# EEZ_DIB_BP3C_r3B1.net
KiCad netlist of a schematic drawn in EAGLE
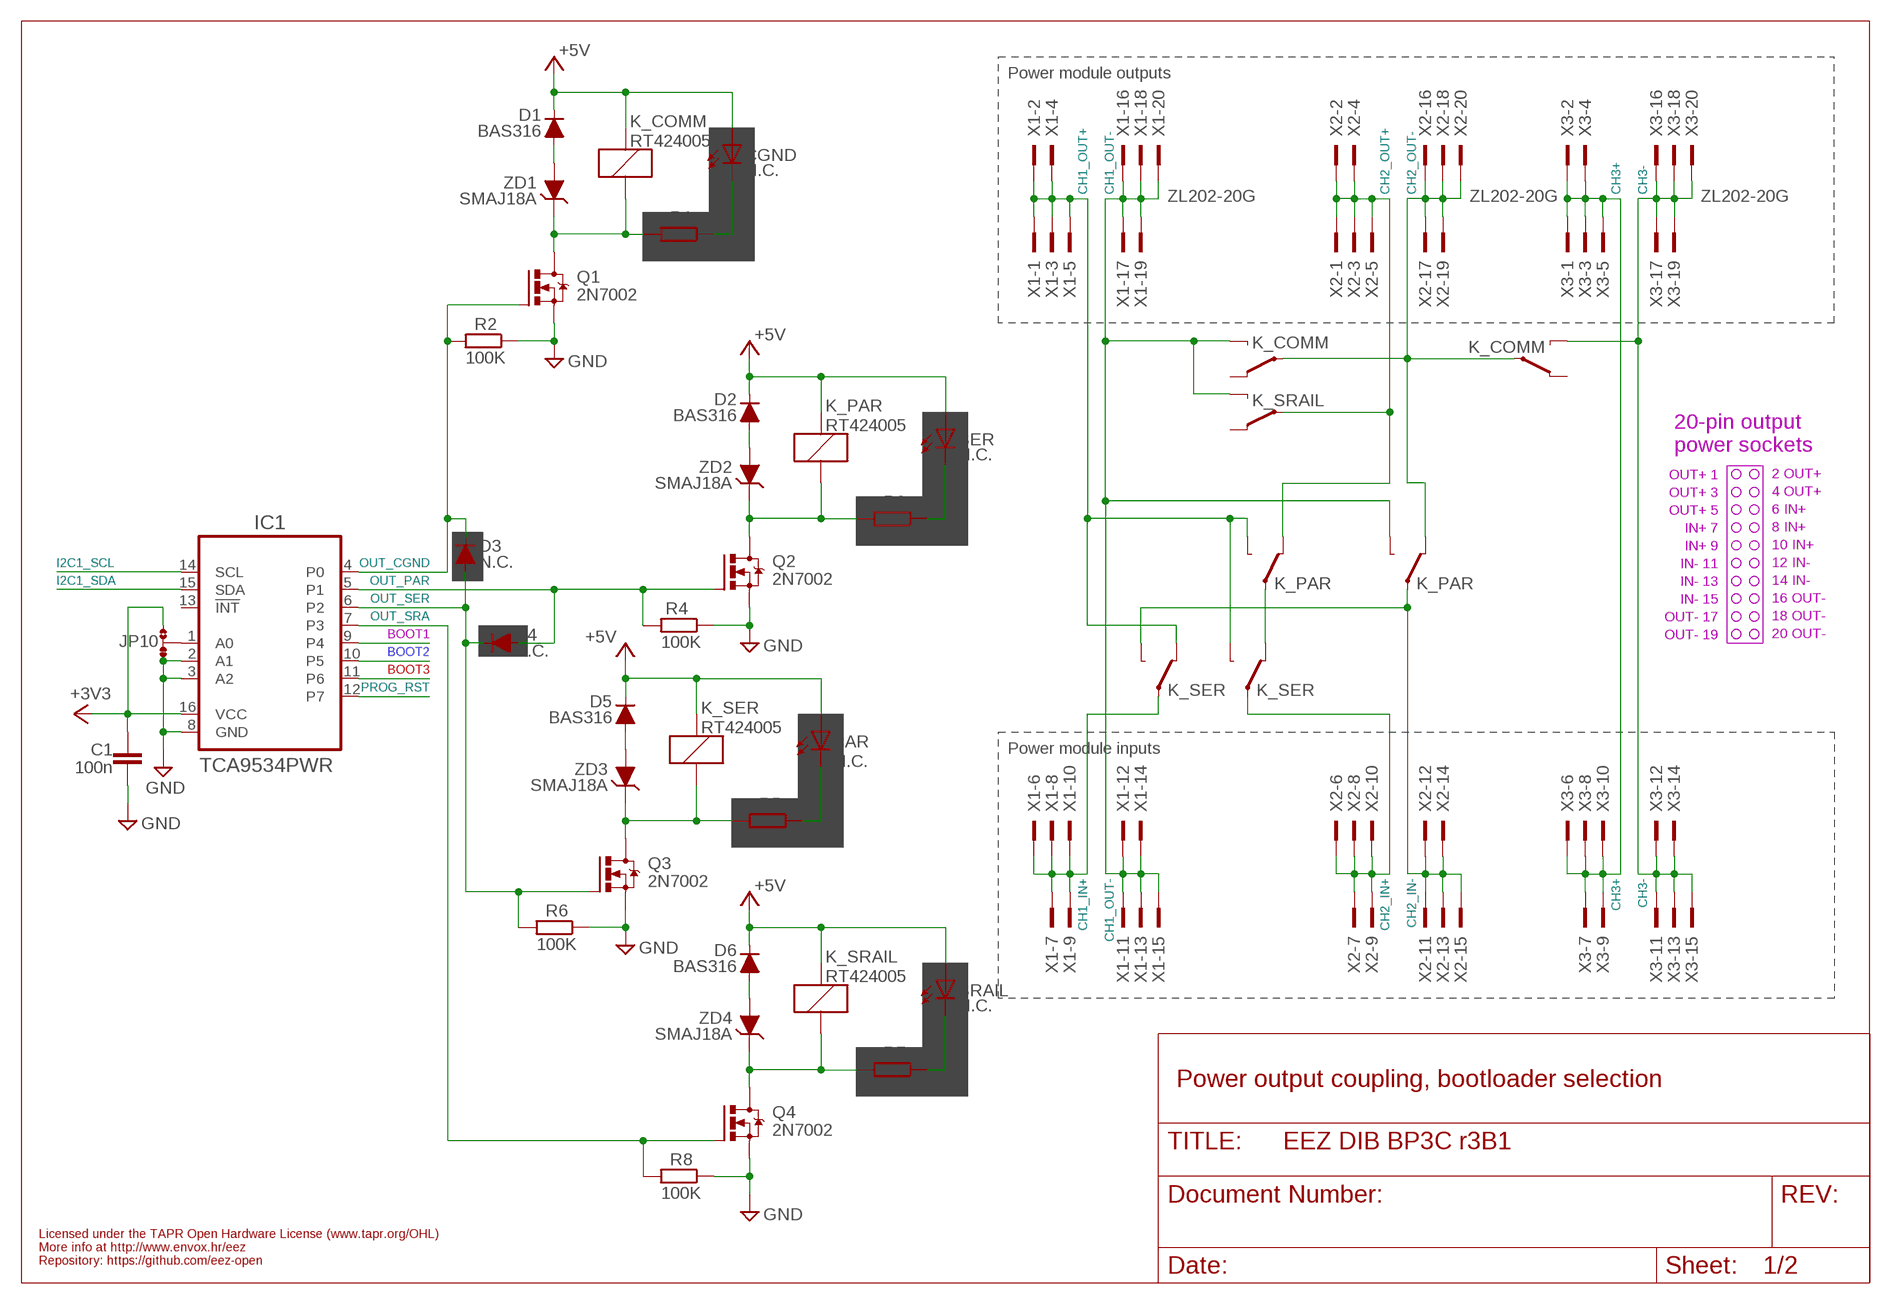
[diagram p0: schematic, sheet 1]
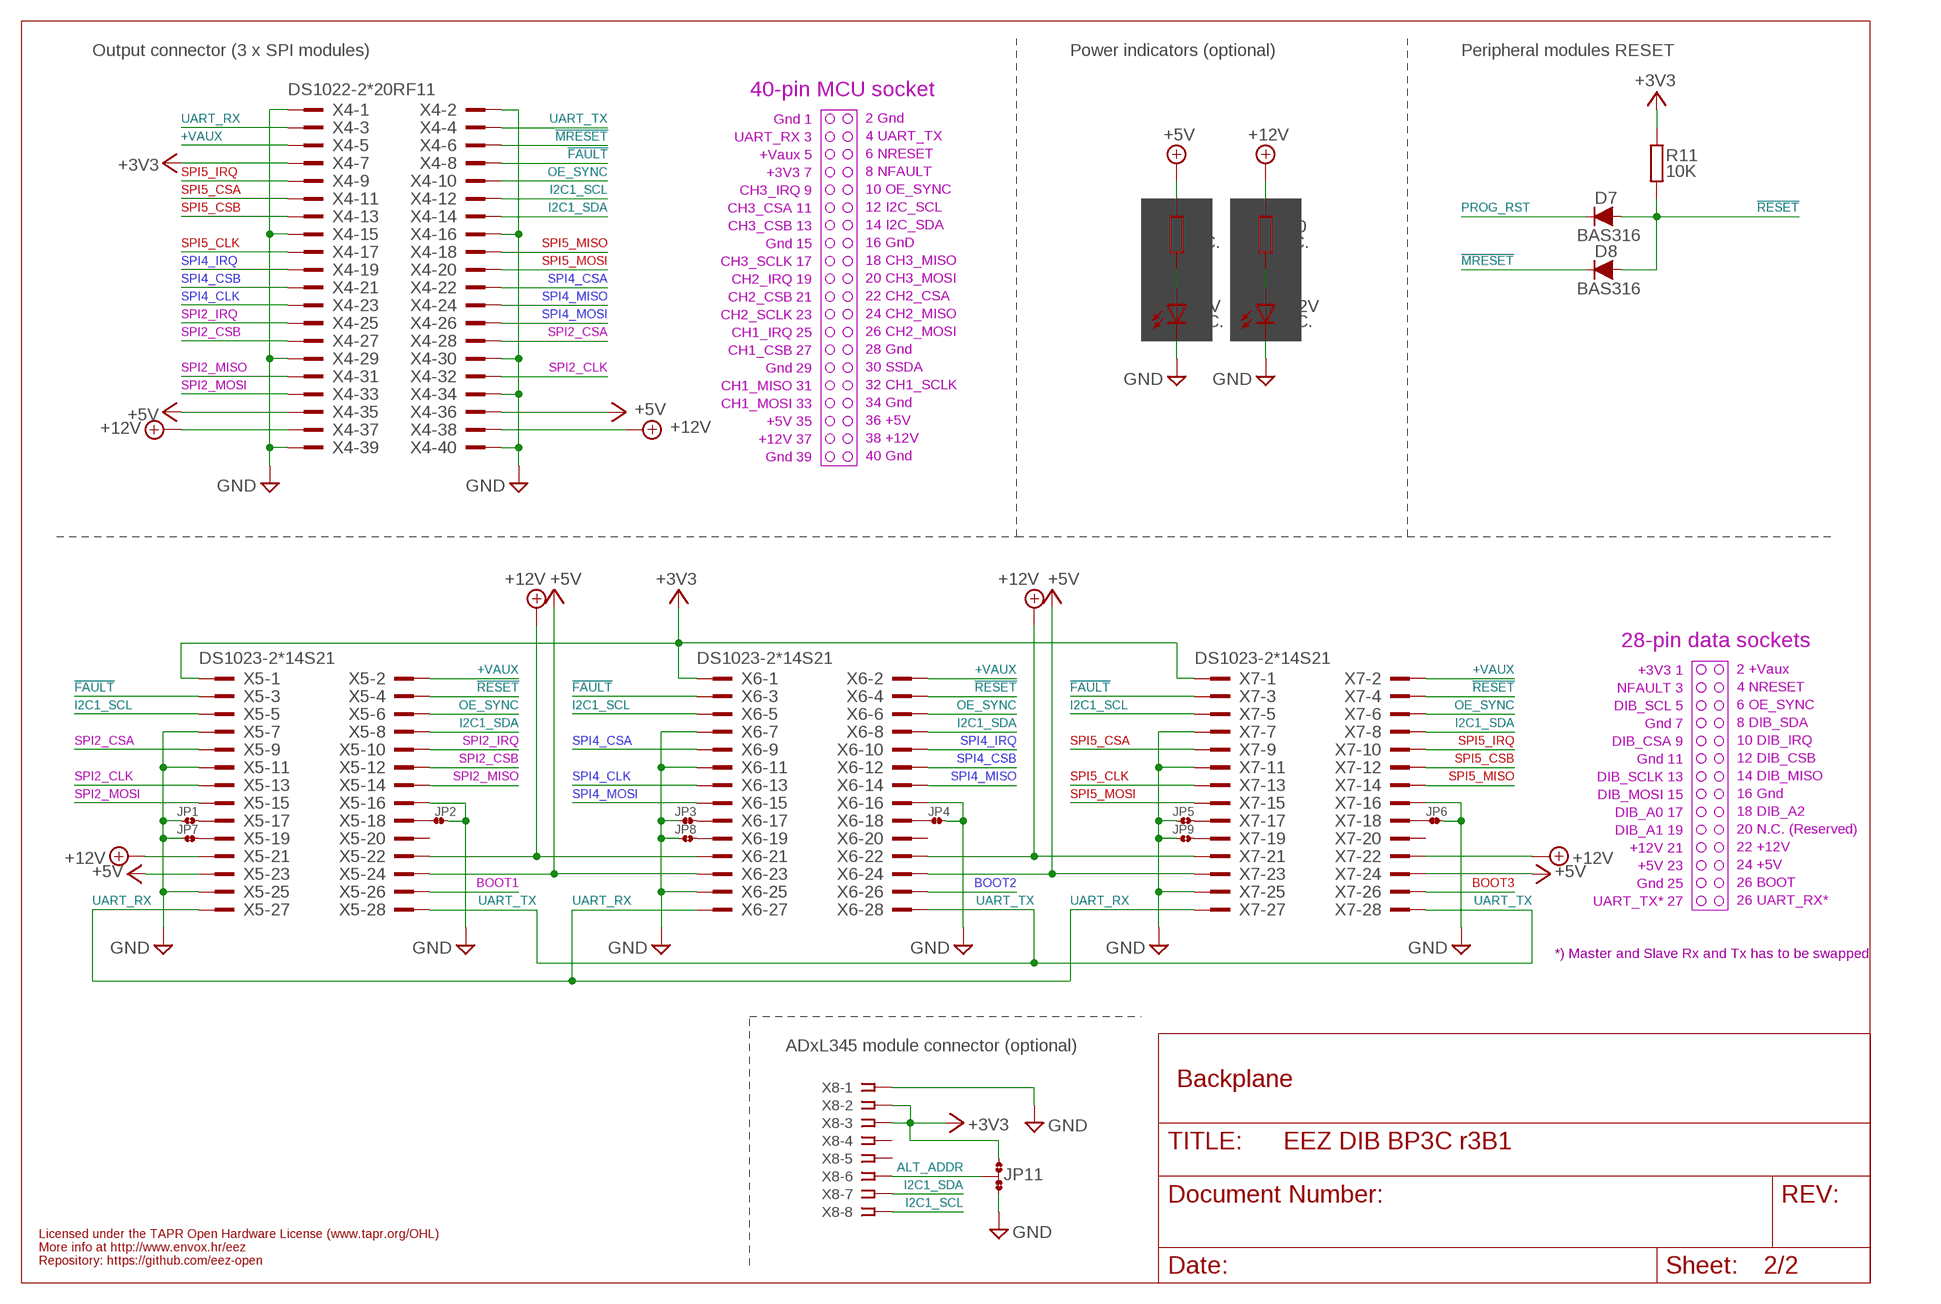
[diagram p1: schematic, sheet 2]

(export (version "E")
  (design (tool "Eeschema 10.0.6"))
  (components
    (comp (ref "+5V")
      (value "N.C.")
      (footprint "eagle-import:LED_0805")
      (libsource (lib "eagle-import") (part "LED0805"))
    )
    (comp (ref "+12V")
      (value "N.C.")
      (footprint "eagle-import:LED_0805")
      (libsource (lib "eagle-import") (part "LED0805"))
    )
    (comp (ref "D7")
      (value "BAS316")
      (footprint "eagle-import:SOD323-R")
      (libsource (lib "eagle-import") (part "DIODESOD323R"))
    )
    (comp (ref "D8")
      (value "BAS316")
      (footprint "eagle-import:SOD323-R")
      (libsource (lib "eagle-import") (part "DIODESOD323R"))
    )
    (comp (ref "JP1")
      (value "JP2-CUT")
      (footprint "eagle-import:JP2-CUT")
      (libsource (lib "eagle-import") (part "JP2-CUT"))
    )
    (comp (ref "JP2")
      (value "JP2-NOCUT")
      (footprint "eagle-import:JP2-NOCUT")
      (libsource (lib "eagle-import") (part "JP2-NOCUT"))
    )
    (comp (ref "JP3")
      (value "JP2-NOCUT")
      (footprint "eagle-import:JP2-NOCUT")
      (libsource (lib "eagle-import") (part "JP2-NOCUT"))
    )
    (comp (ref "JP4")
      (value "JP2-NOCUT")
      (footprint "eagle-import:JP2-NOCUT")
      (libsource (lib "eagle-import") (part "JP2-NOCUT"))
    )
    (comp (ref "JP5")
      (value "JP2-CUT")
      (footprint "eagle-import:JP2-CUT")
      (libsource (lib "eagle-import") (part "JP2-CUT"))
    )
    (comp (ref "JP6")
      (value "JP2-NOCUT")
      (footprint "eagle-import:JP2-NOCUT")
      (libsource (lib "eagle-import") (part "JP2-NOCUT"))
    )
    (comp (ref "JP7")
      (value "JP2-NOCUT")
      (footprint "eagle-import:JP2-NOCUT")
      (libsource (lib "eagle-import") (part "JP2-NOCUT"))
    )
    (comp (ref "JP8")
      (value "JP2-CUT")
      (footprint "eagle-import:JP2-CUT")
      (libsource (lib "eagle-import") (part "JP2-CUT"))
    )
    (comp (ref "JP9")
      (value "JP2-CUT")
      (footprint "eagle-import:JP2-CUT")
      (libsource (lib "eagle-import") (part "JP2-CUT"))
    )
    (comp (ref "JP11")
      (value "JP3-CUT")
      (footprint "eagle-import:JP3-CUT")
      (libsource (lib "eagle-import") (part "JP3-CUT"))
    )
    (comp (ref "R9")
      (value "N.C.")
      (footprint "eagle-import:R0805")
      (libsource (lib "eagle-import") (part "R-EU_R0805"))
    )
    (comp (ref "R10")
      (value "N.C.")
      (footprint "eagle-import:R0805")
      (libsource (lib "eagle-import") (part "R-EU_R0805"))
    )
    (comp (ref "R11")
      (value "10K")
      (footprint "eagle-import:R0805")
      (libsource (lib "eagle-import") (part "R-EU_R0805"))
    )
    (comp (ref "X4")
      (value "DS1022-2*20RF11")
      (footprint "eagle-import:ZL212-40KG")
      (libsource (lib "eagle-import") (part "ZL212-40KG"))
    )
    (comp (ref "X5")
      (value "DS1023-2*14S21")
      (footprint "eagle-import:TSW-114-07-F-D")
      (libsource (lib "eagle-import") (part "TSW-114-07-F-D"))
    )
    (comp (ref "X6")
      (value "DS1023-2*14S21")
      (footprint "eagle-import:TSW-114-07-F-D")
      (libsource (lib "eagle-import") (part "TSW-114-07-F-D"))
    )
    (comp (ref "X7")
      (value "DS1023-2*14S21")
      (footprint "eagle-import:TSW-114-07-F-D")
      (libsource (lib "eagle-import") (part "TSW-114-07-F-D"))
    )
    (comp (ref "X8")
      (value "N.C.")
      (footprint "eagle-import:SSW-108-02-S-S")
      (fields (field (name "MPN") "SSW-108-02-S-S"))
      (libsource (lib "eagle-import") (part "SSW-108-02-S-S"))
    )
    (comp (ref "C1")
      (value "100n")
      (footprint "eagle-import:C0603")
      (libsource (lib "eagle-import") (part "C-EUC0603"))
    )
    (comp (ref "CGND")
      (value "N.C.")
      (footprint "eagle-import:LED_0805")
      (libsource (lib "eagle-import") (part "LED0805"))
    )
    (comp (ref "D1")
      (value "BAS316")
      (footprint "eagle-import:SOD323-R")
      (libsource (lib "eagle-import") (part "DIODESOD323R"))
    )
    (comp (ref "D2")
      (value "BAS316")
      (footprint "eagle-import:SOD323-R")
      (libsource (lib "eagle-import") (part "DIODESOD323R"))
    )
    (comp (ref "D3")
      (value "N.C.")
      (footprint "eagle-import:SOD323-R")
      (libsource (lib "eagle-import") (part "DIODESOD323R"))
    )
    (comp (ref "D4")
      (value "N.C.")
      (footprint "eagle-import:SOD323-R")
      (libsource (lib "eagle-import") (part "DIODESOD323R"))
    )
    (comp (ref "D5")
      (value "BAS316")
      (footprint "eagle-import:SOD323-R")
      (libsource (lib "eagle-import") (part "DIODESOD323R"))
    )
    (comp (ref "D6")
      (value "BAS316")
      (footprint "eagle-import:SOD323-R")
      (libsource (lib "eagle-import") (part "DIODESOD323R"))
    )
    (comp (ref "IC1")
      (value "TCA9534PWR")
      (footprint "eagle-import:PW(R-PDSO-G16)")
      (libsource (lib "eagle-import") (part "TCA9534PWR"))
    )
    (comp (ref "JP10")
      (value "JP3-CUT")
      (footprint "eagle-import:JP3-CUT")
      (libsource (lib "eagle-import") (part "JP3-CUT"))
    )
    (comp (ref "K_COMM")
      (value "RT424005")
      (footprint "eagle-import:RT-C_016A5_ROUND")
      (libsource (lib "eagle-import") (part "RELAY_RT314012-2"))
    )
    (comp (ref "K_PAR")
      (value "RT424005")
      (footprint "eagle-import:RT-C_016A5_ROUND")
      (libsource (lib "eagle-import") (part "RELAY_RT314012-2"))
    )
    (comp (ref "K_SER")
      (value "RT424005")
      (footprint "eagle-import:RT-C_016A5_ROUND")
      (libsource (lib "eagle-import") (part "RELAY_RT314012-2"))
    )
    (comp (ref "K_SRAIL")
      (value "RT424005")
      (footprint "eagle-import:RT-C_016A5_ROUND")
      (libsource (lib "eagle-import") (part "RELAY_RT314012-2"))
    )
    (comp (ref "PAR")
      (value "N.C.")
      (footprint "eagle-import:LED_0805")
      (libsource (lib "eagle-import") (part "LED0805"))
    )
    (comp (ref "Q1")
      (value "2N7002")
      (footprint "eagle-import:SOT103P240X110-3N")
      (fields
        (field (name "MPN") "2N7002-7-F")
        (field (name "MPN_1") "2N7002-7-F")
        (field (name "OC_FARNELL") "1713823")
        (field (name "OC_NEWARK") "25R5679")
        (field (name "PACKAGE") "SOT-23-3")
        (field (name "SUPPLIER") "DIODES INC.")
      )
      (libsource (lib "eagle-import") (part "2N7002"))
    )
    (comp (ref "Q2")
      (value "2N7002")
      (footprint "eagle-import:SOT103P240X110-3N")
      (fields
        (field (name "MPN") "2N7002-7-F")
        (field (name "MPN_1") "2N7002-7-F")
        (field (name "OC_FARNELL") "1713823")
        (field (name "OC_NEWARK") "25R5679")
        (field (name "PACKAGE") "SOT-23-3")
        (field (name "SUPPLIER") "DIODES INC.")
      )
      (libsource (lib "eagle-import") (part "2N7002"))
    )
    (comp (ref "Q3")
      (value "2N7002")
      (footprint "eagle-import:SOT103P240X110-3N")
      (fields
        (field (name "MPN") "2N7002-7-F")
        (field (name "MPN_1") "2N7002-7-F")
        (field (name "OC_FARNELL") "1713823")
        (field (name "OC_NEWARK") "25R5679")
        (field (name "PACKAGE") "SOT-23-3")
        (field (name "SUPPLIER") "DIODES INC.")
      )
      (libsource (lib "eagle-import") (part "2N7002"))
    )
    (comp (ref "Q4")
      (value "2N7002")
      (footprint "eagle-import:SOT103P240X110-3N")
      (fields
        (field (name "MPN") "2N7002-7-F")
        (field (name "MPN_1") "2N7002-7-F")
        (field (name "OC_FARNELL") "1713823")
        (field (name "OC_NEWARK") "25R5679")
        (field (name "PACKAGE") "SOT-23-3")
        (field (name "SUPPLIER") "DIODES INC.")
      )
      (libsource (lib "eagle-import") (part "2N7002"))
    )
    (comp (ref "R1")
      (value "N.C.")
      (footprint "eagle-import:R0805")
      (libsource (lib "eagle-import") (part "R-EU_R0805"))
    )
    (comp (ref "R2")
      (value "100K")
      (footprint "eagle-import:R0805")
      (libsource (lib "eagle-import") (part "R-EU_R0805"))
    )
    (comp (ref "R3")
      (value "N.C.")
      (footprint "eagle-import:R0805")
      (libsource (lib "eagle-import") (part "R-EU_R0805"))
    )
    (comp (ref "R4")
      (value "100K")
      (footprint "eagle-import:R0805")
      (libsource (lib "eagle-import") (part "R-EU_R0805"))
    )
    (comp (ref "R5")
      (value "N.C.")
      (footprint "eagle-import:R0805")
      (libsource (lib "eagle-import") (part "R-EU_R0805"))
    )
    (comp (ref "R6")
      (value "100K")
      (footprint "eagle-import:R0805")
      (libsource (lib "eagle-import") (part "R-EU_R0805"))
    )
    (comp (ref "R7")
      (value "N.C.")
      (footprint "eagle-import:R0805")
      (libsource (lib "eagle-import") (part "R-EU_R0805"))
    )
    (comp (ref "R8")
      (value "100K")
      (footprint "eagle-import:R0805")
      (libsource (lib "eagle-import") (part "R-EU_R0805"))
    )
    (comp (ref "SER")
      (value "N.C.")
      (footprint "eagle-import:LED_0805")
      (libsource (lib "eagle-import") (part "LED0805"))
    )
    (comp (ref "SRAIL")
      (value "N.C.")
      (footprint "eagle-import:LED_0805")
      (libsource (lib "eagle-import") (part "LED0805"))
    )
    (comp (ref "X1")
      (value "ZL202-20G")
      (footprint "eagle-import:DS1021-2_10SF11")
      (libsource (lib "eagle-import") (part "DS1021-210SF11"))
    )
    (comp (ref "X2")
      (value "ZL202-20G")
      (footprint "eagle-import:DS1021-2_10SF11")
      (libsource (lib "eagle-import") (part "DS1021-210SF11"))
    )
    (comp (ref "X3")
      (value "ZL202-20G")
      (footprint "eagle-import:DS1021-2_10SF11")
      (libsource (lib "eagle-import") (part "DS1021-210SF11"))
    )
    (comp (ref "ZD1")
      (value "SMAJ18A")
      (footprint "eagle-import:DO214AC")
      (libsource (lib "eagle-import") (part "PSMAXX"))
    )
    (comp (ref "ZD2")
      (value "SMAJ18A")
      (footprint "eagle-import:DO214AC")
      (libsource (lib "eagle-import") (part "PSMAXX"))
    )
    (comp (ref "ZD3")
      (value "SMAJ18A")
      (footprint "eagle-import:DO214AC")
      (libsource (lib "eagle-import") (part "PSMAXX"))
    )
    (comp (ref "ZD4")
      (value "SMAJ18A")
      (footprint "eagle-import:DO214AC")
      (libsource (lib "eagle-import") (part "PSMAXX"))
    )
  )
  (nets
    (net (code "1") (name "+3V3") (class "Default")
      (node (ref "C1") (pin "1") (pinfunction "1_1") (pintype "passive"))
      (node (ref "IC1") (pin "16") (pinfunction "VCC_16") (pintype "passive"))
      (node (ref "JP10") (pin "NO") (pinfunction "NO_NO") (pintype "passive"))
      (node (ref "JP11") (pin "NO") (pinfunction "NO_NO") (pintype "passive"))
      (node (ref "R11") (pin "1") (pinfunction "1_1") (pintype "passive"))
      (node (ref "X4") (pin "7") (pinfunction "1_7") (pintype "passive"))
      (node (ref "X5") (pin "1") (pinfunction "1_1") (pintype "passive"))
      (node (ref "X6") (pin "1") (pinfunction "1_1") (pintype "passive"))
      (node (ref "X7") (pin "1") (pinfunction "1_1") (pintype "passive"))
      (node (ref "X8") (pin "2") (pinfunction "1_2") (pintype "passive"))
      (node (ref "X8") (pin "3") (pinfunction "1_3") (pintype "passive"))
    )
    (net (code "2") (name "+5V") (class "Default")
      (node (ref "CGND") (pin "A") (pinfunction "A_A") (pintype "passive"))
      (node (ref "D1") (pin "C") (pinfunction "C_C") (pintype "passive"))
      (node (ref "D2") (pin "C") (pinfunction "C_C") (pintype "passive"))
      (node (ref "D5") (pin "C") (pinfunction "C_C") (pintype "passive"))
      (node (ref "D6") (pin "C") (pinfunction "C_C") (pintype "passive"))
      (node (ref "K_COMM") (pin "A2") (pinfunction "C1_A2") (pintype "passive"))
      (node (ref "K_PAR") (pin "A2") (pinfunction "C1_A2") (pintype "passive"))
      (node (ref "K_SER") (pin "A2") (pinfunction "C1_A2") (pintype "passive"))
      (node (ref "K_SRAIL") (pin "A2") (pinfunction "C1_A2") (pintype "passive"))
      (node (ref "PAR") (pin "A") (pinfunction "A_A") (pintype "passive"))
      (node (ref "R9") (pin "1") (pinfunction "1_1") (pintype "passive"))
      (node (ref "SER") (pin "A") (pinfunction "A_A") (pintype "passive"))
      (node (ref "SRAIL") (pin "A") (pinfunction "A_A") (pintype "passive"))
      (node (ref "X4") (pin "35") (pinfunction "1_35") (pintype "passive"))
      (node (ref "X4") (pin "36") (pinfunction "1_36") (pintype "passive"))
      (node (ref "X5") (pin "23") (pinfunction "1_23") (pintype "passive"))
      (node (ref "X5") (pin "24") (pinfunction "1_24") (pintype "passive"))
      (node (ref "X6") (pin "23") (pinfunction "1_23") (pintype "passive"))
      (node (ref "X6") (pin "24") (pinfunction "1_24") (pintype "passive"))
      (node (ref "X7") (pin "23") (pinfunction "1_23") (pintype "passive"))
      (node (ref "X7") (pin "24") (pinfunction "1_24") (pintype "passive"))
    )
    (net (code "3") (name "+12V") (class "Default")
      (node (ref "R10") (pin "1") (pinfunction "1_1") (pintype "passive"))
      (node (ref "X4") (pin "37") (pinfunction "1_37") (pintype "passive"))
      (node (ref "X4") (pin "38") (pinfunction "1_38") (pintype "passive"))
      (node (ref "X5") (pin "21") (pinfunction "1_21") (pintype "passive"))
      (node (ref "X5") (pin "22") (pinfunction "1_22") (pintype "passive"))
      (node (ref "X6") (pin "21") (pinfunction "1_21") (pintype "passive"))
      (node (ref "X6") (pin "22") (pinfunction "1_22") (pintype "passive"))
      (node (ref "X7") (pin "21") (pinfunction "1_21") (pintype "passive"))
      (node (ref "X7") (pin "22") (pinfunction "1_22") (pintype "passive"))
    )
    (net (code "4") (name "+VAUX") (class "Default")
      (node (ref "X4") (pin "5") (pinfunction "1_5") (pintype "passive"))
      (node (ref "X5") (pin "2") (pinfunction "1_2") (pintype "passive"))
      (node (ref "X6") (pin "2") (pinfunction "1_2") (pintype "passive"))
      (node (ref "X7") (pin "2") (pinfunction "1_2") (pintype "passive"))
    )
    (net (code "5") (name "ALT_ADDR") (class "Default")
      (node (ref "JP11") (pin "COM") (pinfunction "COM_COM") (pintype "passive"))
      (node (ref "X8") (pin "6") (pinfunction "1_6") (pintype "passive"))
    )
    (net (code "6") (name "BOOT1") (class "Default")
      (node (ref "IC1") (pin "9") (pinfunction "P4_9") (pintype "bidirectional"))
      (node (ref "X5") (pin "26") (pinfunction "1_26") (pintype "passive"))
    )
    (net (code "7") (name "BOOT2") (class "Default")
      (node (ref "IC1") (pin "10") (pinfunction "P5_10") (pintype "bidirectional"))
      (node (ref "X6") (pin "26") (pinfunction "1_26") (pintype "passive"))
    )
    (net (code "8") (name "BOOT3") (class "Default")
      (node (ref "IC1") (pin "11") (pinfunction "P6_11") (pintype "bidirectional"))
      (node (ref "X7") (pin "26") (pinfunction "1_26") (pintype "passive"))
    )
    (net (code "9") (name "CH1_IN+") (class "Default")
      (node (ref "K_SER") (pin "11A") (pinfunction "P_11A") (pintype "passive"))
      (node (ref "X1") (pin "10") (pinfunction "1_10") (pintype "passive"))
      (node (ref "X1") (pin "6") (pinfunction "1_6") (pintype "passive"))
      (node (ref "X1") (pin "7") (pinfunction "1_7") (pintype "passive"))
      (node (ref "X1") (pin "8") (pinfunction "1_8") (pintype "passive"))
      (node (ref "X1") (pin "9") (pinfunction "1_9") (pintype "passive"))
    )
    (net (code "10") (name "CH1_OUT+") (class "Default")
      (node (ref "K_PAR") (pin "14A") (pinfunction "O_14A") (pintype "passive"))
      (node (ref "K_SER") (pin "12A") (pinfunction "S_12A") (pintype "passive"))
      (node (ref "K_SER") (pin "14B") (pinfunction "O_14B") (pintype "passive"))
      (node (ref "X1") (pin "1") (pinfunction "1_1") (pintype "passive"))
      (node (ref "X1") (pin "2") (pinfunction "1_2") (pintype "passive"))
      (node (ref "X1") (pin "3") (pinfunction "1_3") (pintype "passive"))
      (node (ref "X1") (pin "4") (pinfunction "1_4") (pintype "passive"))
      (node (ref "X1") (pin "5") (pinfunction "1_5") (pintype "passive"))
    )
    (net (code "11") (name "CH1_OUT-") (class "Default")
      (node (ref "K_COMM") (pin "14A") (pinfunction "O_14A") (pintype "passive"))
      (node (ref "K_PAR") (pin "14B") (pinfunction "O_14B") (pintype "passive"))
      (node (ref "K_SRAIL") (pin "14A") (pinfunction "O_14A") (pintype "passive"))
      (node (ref "X1") (pin "11") (pinfunction "1_11") (pintype "passive"))
      (node (ref "X1") (pin "12") (pinfunction "1_12") (pintype "passive"))
      (node (ref "X1") (pin "13") (pinfunction "1_13") (pintype "passive"))
      (node (ref "X1") (pin "14") (pinfunction "1_14") (pintype "passive"))
      (node (ref "X1") (pin "15") (pinfunction "1_15") (pintype "passive"))
      (node (ref "X1") (pin "16") (pinfunction "1_16") (pintype "passive"))
      (node (ref "X1") (pin "17") (pinfunction "1_17") (pintype "passive"))
      (node (ref "X1") (pin "18") (pinfunction "1_18") (pintype "passive"))
      (node (ref "X1") (pin "19") (pinfunction "1_19") (pintype "passive"))
      (node (ref "X1") (pin "20") (pinfunction "1_20") (pintype "passive"))
    )
    (net (code "12") (name "CH2_IN+") (class "Default")
      (node (ref "K_SER") (pin "11B") (pinfunction "P_11B") (pintype "passive"))
      (node (ref "X2") (pin "10") (pinfunction "1_10") (pintype "passive"))
      (node (ref "X2") (pin "6") (pinfunction "1_6") (pintype "passive"))
      (node (ref "X2") (pin "7") (pinfunction "1_7") (pintype "passive"))
      (node (ref "X2") (pin "8") (pinfunction "1_8") (pintype "passive"))
      (node (ref "X2") (pin "9") (pinfunction "1_9") (pintype "passive"))
    )
    (net (code "13") (name "CH2_IN-") (class "Default")
      (node (ref "K_PAR") (pin "11B") (pinfunction "P_11B") (pintype "passive"))
      (node (ref "K_SER") (pin "14A") (pinfunction "O_14A") (pintype "passive"))
      (node (ref "X2") (pin "11") (pinfunction "1_11") (pintype "passive"))
      (node (ref "X2") (pin "12") (pinfunction "1_12") (pintype "passive"))
      (node (ref "X2") (pin "13") (pinfunction "1_13") (pintype "passive"))
      (node (ref "X2") (pin "14") (pinfunction "1_14") (pintype "passive"))
      (node (ref "X2") (pin "15") (pinfunction "1_15") (pintype "passive"))
    )
    (net (code "14") (name "CH2_OUT+") (class "Default")
      (node (ref "K_PAR") (pin "12A") (pinfunction "S_12A") (pintype "passive"))
      (node (ref "K_SRAIL") (pin "11A") (pinfunction "P_11A") (pintype "passive"))
      (node (ref "X2") (pin "1") (pinfunction "1_1") (pintype "passive"))
      (node (ref "X2") (pin "2") (pinfunction "1_2") (pintype "passive"))
      (node (ref "X2") (pin "3") (pinfunction "1_3") (pintype "passive"))
      (node (ref "X2") (pin "4") (pinfunction "1_4") (pintype "passive"))
      (node (ref "X2") (pin "5") (pinfunction "1_5") (pintype "passive"))
    )
    (net (code "15") (name "CH2_OUT-") (class "Default")
      (node (ref "K_COMM") (pin "11A") (pinfunction "P_11A") (pintype "passive"))
      (node (ref "K_COMM") (pin "11B") (pinfunction "P_11B") (pintype "passive"))
      (node (ref "K_PAR") (pin "12B") (pinfunction "S_12B") (pintype "passive"))
      (node (ref "X2") (pin "16") (pinfunction "1_16") (pintype "passive"))
      (node (ref "X2") (pin "17") (pinfunction "1_17") (pintype "passive"))
      (node (ref "X2") (pin "18") (pinfunction "1_18") (pintype "passive"))
      (node (ref "X2") (pin "19") (pinfunction "1_19") (pintype "passive"))
      (node (ref "X2") (pin "20") (pinfunction "1_20") (pintype "passive"))
    )
    (net (code "16") (name "CH3+") (class "Default")
      (node (ref "X3") (pin "1") (pinfunction "1_1") (pintype "passive"))
      (node (ref "X3") (pin "10") (pinfunction "1_10") (pintype "passive"))
      (node (ref "X3") (pin "2") (pinfunction "1_2") (pintype "passive"))
      (node (ref "X3") (pin "3") (pinfunction "1_3") (pintype "passive"))
      (node (ref "X3") (pin "4") (pinfunction "1_4") (pintype "passive"))
      (node (ref "X3") (pin "5") (pinfunction "1_5") (pintype "passive"))
      (node (ref "X3") (pin "6") (pinfunction "1_6") (pintype "passive"))
      (node (ref "X3") (pin "7") (pinfunction "1_7") (pintype "passive"))
      (node (ref "X3") (pin "8") (pinfunction "1_8") (pintype "passive"))
      (node (ref "X3") (pin "9") (pinfunction "1_9") (pintype "passive"))
    )
    (net (code "17") (name "CH3-") (class "Default")
      (node (ref "K_COMM") (pin "14B") (pinfunction "O_14B") (pintype "passive"))
      (node (ref "X3") (pin "11") (pinfunction "1_11") (pintype "passive"))
      (node (ref "X3") (pin "12") (pinfunction "1_12") (pintype "passive"))
      (node (ref "X3") (pin "13") (pinfunction "1_13") (pintype "passive"))
      (node (ref "X3") (pin "14") (pinfunction "1_14") (pintype "passive"))
      (node (ref "X3") (pin "15") (pinfunction "1_15") (pintype "passive"))
      (node (ref "X3") (pin "16") (pinfunction "1_16") (pintype "passive"))
      (node (ref "X3") (pin "17") (pinfunction "1_17") (pintype "passive"))
      (node (ref "X3") (pin "18") (pinfunction "1_18") (pintype "passive"))
      (node (ref "X3") (pin "19") (pinfunction "1_19") (pintype "passive"))
      (node (ref "X3") (pin "20") (pinfunction "1_20") (pintype "passive"))
    )
    (net (code "18") (name "GND") (class "Default")
      (node (ref "+12V") (pin "C") (pinfunction "C_C") (pintype "passive"))
      (node (ref "+5V") (pin "C") (pinfunction "C_C") (pintype "passive"))
      (node (ref "C1") (pin "2") (pinfunction "2_2") (pintype "passive"))
      (node (ref "IC1") (pin "2") (pinfunction "A1_2") (pintype "input"))
      (node (ref "IC1") (pin "3") (pinfunction "A2_3") (pintype "input"))
      (node (ref "IC1") (pin "8") (pinfunction "GND_8") (pintype "passive"))
      (node (ref "JP1") (pin "1") (pinfunction "1_1") (pintype "passive"))
      (node (ref "JP10") (pin "NC") (pinfunction "NC_NC") (pintype "passive"))
      (node (ref "JP11") (pin "NC") (pinfunction "NC_NC") (pintype "passive"))
      (node (ref "JP2") (pin "2") (pinfunction "2_2") (pintype "passive"))
      (node (ref "JP3") (pin "1") (pinfunction "1_1") (pintype "passive"))
      (node (ref "JP4") (pin "2") (pinfunction "2_2") (pintype "passive"))
      (node (ref "JP5") (pin "1") (pinfunction "1_1") (pintype "passive"))
      (node (ref "JP6") (pin "2") (pinfunction "2_2") (pintype "passive"))
      (node (ref "JP7") (pin "1") (pinfunction "1_1") (pintype "passive"))
      (node (ref "JP8") (pin "1") (pinfunction "1_1") (pintype "passive"))
      (node (ref "JP9") (pin "1") (pinfunction "1_1") (pintype "passive"))
      (node (ref "Q1") (pin "2") (pinfunction "S_2") (pintype "passive"))
      (node (ref "Q2") (pin "2") (pinfunction "S_2") (pintype "passive"))
      (node (ref "Q3") (pin "2") (pinfunction "S_2") (pintype "passive"))
      (node (ref "Q4") (pin "2") (pinfunction "S_2") (pintype "passive"))
      (node (ref "R2") (pin "1") (pinfunction "1_1") (pintype "passive"))
      (node (ref "R4") (pin "1") (pinfunction "1_1") (pintype "passive"))
      (node (ref "R6") (pin "1") (pinfunction "1_1") (pintype "passive"))
      (node (ref "R8") (pin "1") (pinfunction "1_1") (pintype "passive"))
      (node (ref "X4") (pin "1") (pinfunction "1_1") (pintype "passive"))
      (node (ref "X4") (pin "15") (pinfunction "1_15") (pintype "passive"))
      (node (ref "X4") (pin "16") (pinfunction "1_16") (pintype "passive"))
      (node (ref "X4") (pin "2") (pinfunction "1_2") (pintype "passive"))
      (node (ref "X4") (pin "29") (pinfunction "1_29") (pintype "passive"))
      (node (ref "X4") (pin "30") (pinfunction "1_30") (pintype "passive"))
      (node (ref "X4") (pin "34") (pinfunction "1_34") (pintype "passive"))
      (node (ref "X4") (pin "39") (pinfunction "1_39") (pintype "passive"))
      (node (ref "X4") (pin "40") (pinfunction "1_40") (pintype "passive"))
      (node (ref "X5") (pin "11") (pinfunction "1_11") (pintype "passive"))
      (node (ref "X5") (pin "16") (pinfunction "1_16") (pintype "passive"))
      (node (ref "X5") (pin "25") (pinfunction "1_25") (pintype "passive"))
      (node (ref "X5") (pin "7") (pinfunction "1_7") (pintype "passive"))
      (node (ref "X6") (pin "11") (pinfunction "1_11") (pintype "passive"))
      (node (ref "X6") (pin "16") (pinfunction "1_16") (pintype "passive"))
      (node (ref "X6") (pin "25") (pinfunction "1_25") (pintype "passive"))
      (node (ref "X6") (pin "7") (pinfunction "1_7") (pintype "passive"))
      (node (ref "X7") (pin "11") (pinfunction "1_11") (pintype "passive"))
      (node (ref "X7") (pin "16") (pinfunction "1_16") (pintype "passive"))
      (node (ref "X7") (pin "25") (pinfunction "1_25") (pintype "passive"))
      (node (ref "X7") (pin "7") (pinfunction "1_7") (pintype "passive"))
      (node (ref "X8") (pin "1") (pinfunction "1_1") (pintype "passive"))
    )
    (net (code "19") (name "I2C1_SCL") (class "Default")
      (node (ref "IC1") (pin "14") (pinfunction "SCL_14") (pintype "input"))
      (node (ref "X4") (pin "12") (pinfunction "1_12") (pintype "passive"))
      (node (ref "X5") (pin "5") (pinfunction "1_5") (pintype "passive"))
      (node (ref "X6") (pin "5") (pinfunction "1_5") (pintype "passive"))
      (node (ref "X7") (pin "5") (pinfunction "1_5") (pintype "passive"))
      (node (ref "X8") (pin "8") (pinfunction "1_8") (pintype "passive"))
    )
    (net (code "20") (name "I2C1_SDA") (class "Default")
      (node (ref "IC1") (pin "15") (pinfunction "SDA_15") (pintype "bidirectional"))
      (node (ref "X4") (pin "14") (pinfunction "1_14") (pintype "passive"))
      (node (ref "X5") (pin "8") (pinfunction "1_8") (pintype "passive"))
      (node (ref "X6") (pin "8") (pinfunction "1_8") (pintype "passive"))
      (node (ref "X7") (pin "8") (pinfunction "1_8") (pintype "passive"))
      (node (ref "X8") (pin "7") (pinfunction "1_7") (pintype "passive"))
    )
    (net (code "21") (name "Net-(+5V-PadA)") (class "Default")
      (node (ref "+5V") (pin "A") (pinfunction "A_A") (pintype "passive"))
      (node (ref "R9") (pin "2") (pinfunction "2_2") (pintype "passive"))
    )
    (net (code "22") (name "Net-(+12V-PadA)") (class "Default")
      (node (ref "+12V") (pin "A") (pinfunction "A_A") (pintype "passive"))
      (node (ref "R10") (pin "2") (pinfunction "2_2") (pintype "passive"))
    )
    (net (code "23") (name "Net-(CGND-PadC)") (class "Default")
      (node (ref "CGND") (pin "C") (pinfunction "C_C") (pintype "passive"))
      (node (ref "R1") (pin "1") (pinfunction "1_1") (pintype "passive"))
    )
    (net (code "24") (name "Net-(D1-PadA)") (class "Default")
      (node (ref "D1") (pin "A") (pinfunction "A_A") (pintype "passive"))
      (node (ref "ZD1") (pin "A") (pinfunction "A_A") (pintype "passive"))
    )
    (net (code "25") (name "Net-(D2-PadA)") (class "Default")
      (node (ref "D2") (pin "A") (pinfunction "A_A") (pintype "passive"))
      (node (ref "ZD2") (pin "A") (pinfunction "A_A") (pintype "passive"))
    )
    (net (code "26") (name "Net-(D5-PadA)") (class "Default")
      (node (ref "D5") (pin "A") (pinfunction "A_A") (pintype "passive"))
      (node (ref "ZD3") (pin "A") (pinfunction "A_A") (pintype "passive"))
    )
    (net (code "27") (name "Net-(D6-PadA)") (class "Default")
      (node (ref "D6") (pin "A") (pinfunction "A_A") (pintype "passive"))
      (node (ref "ZD4") (pin "A") (pinfunction "A_A") (pintype "passive"))
    )
    (net (code "28") (name "Net-(IC1-A0)") (class "Default")
      (node (ref "IC1") (pin "1") (pinfunction "A0_1") (pintype "input"))
      (node (ref "JP10") (pin "COM") (pinfunction "COM_COM") (pintype "passive"))
    )
    (net (code "29") (name "Net-(K_COMMC-C2)") (class "Default")
      (node (ref "K_COMM") (pin "A1") (pinfunction "C2_A1") (pintype "passive"))
      (node (ref "Q1") (pin "3") (pinfunction "D_3") (pintype "passive"))
      (node (ref "R1") (pin "2") (pinfunction "2_2") (pintype "passive"))
      (node (ref "ZD1") (pin "C") (pinfunction "C_C") (pintype "passive"))
    )
    (net (code "30") (name "Net-(K_PARA-P)") (class "Default")
      (node (ref "K_PAR") (pin "11A") (pinfunction "P_11A") (pintype "passive"))
      (node (ref "K_SER") (pin "12B") (pinfunction "S_12B") (pintype "passive"))
    )
    (net (code "31") (name "Net-(K_PARC-C2)") (class "Default")
      (node (ref "K_PAR") (pin "A1") (pinfunction "C2_A1") (pintype "passive"))
      (node (ref "Q2") (pin "3") (pinfunction "D_3") (pintype "passive"))
      (node (ref "R3") (pin "2") (pinfunction "2_2") (pintype "passive"))
      (node (ref "ZD2") (pin "C") (pinfunction "C_C") (pintype "passive"))
    )
    (net (code "32") (name "Net-(K_SERC-C2)") (class "Default")
      (node (ref "K_SER") (pin "A1") (pinfunction "C2_A1") (pintype "passive"))
      (node (ref "Q3") (pin "3") (pinfunction "D_3") (pintype "passive"))
      (node (ref "R5") (pin "2") (pinfunction "2_2") (pintype "passive"))
      (node (ref "ZD3") (pin "C") (pinfunction "C_C") (pintype "passive"))
    )
    (net (code "33") (name "Net-(K_SRAILC-C2)") (class "Default")
      (node (ref "K_SRAIL") (pin "A1") (pinfunction "C2_A1") (pintype "passive"))
      (node (ref "Q4") (pin "3") (pinfunction "D_3") (pintype "passive"))
      (node (ref "R7") (pin "2") (pinfunction "2_2") (pintype "passive"))
      (node (ref "ZD4") (pin "C") (pinfunction "C_C") (pintype "passive"))
    )
    (net (code "34") (name "Net-(PAR-PadC)") (class "Default")
      (node (ref "PAR") (pin "C") (pinfunction "C_C") (pintype "passive"))
      (node (ref "R5") (pin "1") (pinfunction "1_1") (pintype "passive"))
    )
    (net (code "35") (name "Net-(R3-Pad1)") (class "Default")
      (node (ref "R3") (pin "1") (pinfunction "1_1") (pintype "passive"))
      (node (ref "SER") (pin "C") (pinfunction "C_C") (pintype "passive"))
    )
    (net (code "36") (name "Net-(R7-Pad1)") (class "Default")
      (node (ref "R7") (pin "1") (pinfunction "1_1") (pintype "passive"))
      (node (ref "SRAIL") (pin "C") (pinfunction "C_C") (pintype "passive"))
    )
    (net (code "37") (name "Net-(X5I-1)") (class "Default")
      (node (ref "JP1") (pin "2") (pinfunction "2_2") (pintype "passive"))
      (node (ref "X5") (pin "17") (pinfunction "1_17") (pintype "passive"))
    )
    (net (code "38") (name "Net-(X5J-1)") (class "Default")
      (node (ref "JP2") (pin "1") (pinfunction "1_1") (pintype "passive"))
      (node (ref "X5") (pin "18") (pinfunction "1_18") (pintype "passive"))
    )
    (net (code "39") (name "Net-(X5K-1)") (class "Default")
      (node (ref "JP7") (pin "2") (pinfunction "2_2") (pintype "passive"))
      (node (ref "X5") (pin "19") (pinfunction "1_19") (pintype "passive"))
    )
    (net (code "40") (name "Net-(X6I-1)") (class "Default")
      (node (ref "JP3") (pin "2") (pinfunction "2_2") (pintype "passive"))
      (node (ref "X6") (pin "17") (pinfunction "1_17") (pintype "passive"))
    )
    (net (code "41") (name "Net-(X6J-1)") (class "Default")
      (node (ref "JP4") (pin "1") (pinfunction "1_1") (pintype "passive"))
      (node (ref "X6") (pin "18") (pinfunction "1_18") (pintype "passive"))
    )
    (net (code "42") (name "Net-(X6K-1)") (class "Default")
      (node (ref "JP8") (pin "2") (pinfunction "2_2") (pintype "passive"))
      (node (ref "X6") (pin "19") (pinfunction "1_19") (pintype "passive"))
    )
    (net (code "43") (name "Net-(X7I-1)") (class "Default")
      (node (ref "JP5") (pin "2") (pinfunction "2_2") (pintype "passive"))
      (node (ref "X7") (pin "17") (pinfunction "1_17") (pintype "passive"))
    )
    (net (code "44") (name "Net-(X7J-1)") (class "Default")
      (node (ref "JP6") (pin "1") (pinfunction "1_1") (pintype "passive"))
      (node (ref "X7") (pin "18") (pinfunction "1_18") (pintype "passive"))
    )
    (net (code "45") (name "Net-(X7K-1)") (class "Default")
      (node (ref "JP9") (pin "2") (pinfunction "2_2") (pintype "passive"))
      (node (ref "X7") (pin "19") (pinfunction "1_19") (pintype "passive"))
    )
    (net (code "46") (name "OE_SYNC") (class "Default")
      (node (ref "X4") (pin "10") (pinfunction "1_10") (pintype "passive"))
      (node (ref "X5") (pin "6") (pinfunction "1_6") (pintype "passive"))
      (node (ref "X6") (pin "6") (pinfunction "1_6") (pintype "passive"))
      (node (ref "X7") (pin "6") (pinfunction "1_6") (pintype "passive"))
    )
    (net (code "47") (name "OUT_CGND") (class "Default")
      (node (ref "D3") (pin "C") (pinfunction "C_C") (pintype "passive"))
      (node (ref "IC1") (pin "4") (pinfunction "P0_4") (pintype "bidirectional"))
      (node (ref "Q1") (pin "1") (pinfunction "G_1") (pintype "passive"))
      (node (ref "R2") (pin "2") (pinfunction "2_2") (pintype "passive"))
    )
    (net (code "48") (name "OUT_PAR") (class "Default")
      (node (ref "D4") (pin "A") (pinfunction "A_A") (pintype "passive"))
      (node (ref "IC1") (pin "5") (pinfunction "P1_5") (pintype "bidirectional"))
      (node (ref "Q2") (pin "1") (pinfunction "G_1") (pintype "passive"))
      (node (ref "R4") (pin "2") (pinfunction "2_2") (pintype "passive"))
    )
    (net (code "49") (name "OUT_SER") (class "Default")
      (node (ref "D3") (pin "A") (pinfunction "A_A") (pintype "passive"))
      (node (ref "D4") (pin "C") (pinfunction "C_C") (pintype "passive"))
      (node (ref "IC1") (pin "6") (pinfunction "P2_6") (pintype "bidirectional"))
      (node (ref "Q3") (pin "1") (pinfunction "G_1") (pintype "passive"))
      (node (ref "R6") (pin "2") (pinfunction "2_2") (pintype "passive"))
    )
    (net (code "50") (name "OUT_SRA") (class "Default")
      (node (ref "IC1") (pin "7") (pinfunction "P3_7") (pintype "bidirectional"))
      (node (ref "Q4") (pin "1") (pinfunction "G_1") (pintype "passive"))
      (node (ref "R8") (pin "2") (pinfunction "2_2") (pintype "passive"))
    )
    (net (code "51") (name "PROG_RST") (class "Default")
      (node (ref "D7") (pin "C") (pinfunction "C_C") (pintype "passive"))
      (node (ref "IC1") (pin "12") (pinfunction "P7_12") (pintype "bidirectional"))
    )
    (net (code "52") (name "SPI2_CLK") (class "Default")
      (node (ref "X4") (pin "32") (pinfunction "1_32") (pintype "passive"))
      (node (ref "X5") (pin "13") (pinfunction "1_13") (pintype "passive"))
    )
    (net (code "53") (name "SPI2_CSA") (class "Default")
      (node (ref "X4") (pin "28") (pinfunction "1_28") (pintype "passive"))
      (node (ref "X5") (pin "9") (pinfunction "1_9") (pintype "passive"))
    )
    (net (code "54") (name "SPI2_CSB") (class "Default")
      (node (ref "X4") (pin "27") (pinfunction "1_27") (pintype "passive"))
      (node (ref "X5") (pin "12") (pinfunction "1_12") (pintype "passive"))
    )
    (net (code "55") (name "SPI2_IRQ") (class "Default")
      (node (ref "X4") (pin "25") (pinfunction "1_25") (pintype "passive"))
      (node (ref "X5") (pin "10") (pinfunction "1_10") (pintype "passive"))
    )
    (net (code "56") (name "SPI2_MISO") (class "Default")
      (node (ref "X4") (pin "31") (pinfunction "1_31") (pintype "passive"))
      (node (ref "X5") (pin "14") (pinfunction "1_14") (pintype "passive"))
    )
    (net (code "57") (name "SPI2_MOSI") (class "Default")
      (node (ref "X4") (pin "33") (pinfunction "1_33") (pintype "passive"))
      (node (ref "X5") (pin "15") (pinfunction "1_15") (pintype "passive"))
    )
    (net (code "58") (name "SPI4_CLK") (class "Default")
      (node (ref "X4") (pin "23") (pinfunction "1_23") (pintype "passive"))
      (node (ref "X6") (pin "13") (pinfunction "1_13") (pintype "passive"))
    )
    (net (code "59") (name "SPI4_CSA") (class "Default")
      (node (ref "X4") (pin "22") (pinfunction "1_22") (pintype "passive"))
      (node (ref "X6") (pin "9") (pinfunction "1_9") (pintype "passive"))
    )
    (net (code "60") (name "SPI4_CSB") (class "Default")
      (node (ref "X4") (pin "21") (pinfunction "1_21") (pintype "passive"))
      (node (ref "X6") (pin "12") (pinfunction "1_12") (pintype "passive"))
    )
    (net (code "61") (name "SPI4_IRQ") (class "Default")
      (node (ref "X4") (pin "19") (pinfunction "1_19") (pintype "passive"))
      (node (ref "X6") (pin "10") (pinfunction "1_10") (pintype "passive"))
    )
    (net (code "62") (name "SPI4_MISO") (class "Default")
      (node (ref "X4") (pin "24") (pinfunction "1_24") (pintype "passive"))
      (node (ref "X6") (pin "14") (pinfunction "1_14") (pintype "passive"))
    )
    (net (code "63") (name "SPI4_MOSI") (class "Default")
      (node (ref "X4") (pin "26") (pinfunction "1_26") (pintype "passive"))
      (node (ref "X6") (pin "15") (pinfunction "1_15") (pintype "passive"))
    )
    (net (code "64") (name "SPI5_CLK") (class "Default")
      (node (ref "X4") (pin "17") (pinfunction "1_17") (pintype "passive"))
      (node (ref "X7") (pin "13") (pinfunction "1_13") (pintype "passive"))
    )
    (net (code "65") (name "SPI5_CSA") (class "Default")
      (node (ref "X4") (pin "11") (pinfunction "1_11") (pintype "passive"))
      (node (ref "X7") (pin "9") (pinfunction "1_9") (pintype "passive"))
    )
    (net (code "66") (name "SPI5_CSB") (class "Default")
      (node (ref "X4") (pin "13") (pinfunction "1_13") (pintype "passive"))
      (node (ref "X7") (pin "12") (pinfunction "1_12") (pintype "passive"))
    )
    (net (code "67") (name "SPI5_IRQ") (class "Default")
      (node (ref "X4") (pin "9") (pinfunction "1_9") (pintype "passive"))
      (node (ref "X7") (pin "10") (pinfunction "1_10") (pintype "passive"))
    )
    (net (code "68") (name "SPI5_MISO") (class "Default")
      (node (ref "X4") (pin "18") (pinfunction "1_18") (pintype "passive"))
      (node (ref "X7") (pin "14") (pinfunction "1_14") (pintype "passive"))
    )
    (net (code "69") (name "SPI5_MOSI") (class "Default")
      (node (ref "X4") (pin "20") (pinfunction "1_20") (pintype "passive"))
      (node (ref "X7") (pin "15") (pinfunction "1_15") (pintype "passive"))
    )
    (net (code "70") (name "UART_RX") (class "Default")
      (node (ref "X4") (pin "3") (pinfunction "1_3") (pintype "passive"))
      (node (ref "X5") (pin "27") (pinfunction "1_27") (pintype "passive"))
      (node (ref "X6") (pin "27") (pinfunction "1_27") (pintype "passive"))
      (node (ref "X7") (pin "27") (pinfunction "1_27") (pintype "passive"))
    )
    (net (code "71") (name "UART_TX") (class "Default")
      (node (ref "X4") (pin "4") (pinfunction "1_4") (pintype "passive"))
      (node (ref "X5") (pin "28") (pinfunction "1_28") (pintype "passive"))
      (node (ref "X6") (pin "28") (pinfunction "1_28") (pintype "passive"))
      (node (ref "X7") (pin "28") (pinfunction "1_28") (pintype "passive"))
    )
    (net (code "72") (name "unconnected-(IC1-~{INT}-Pad13)") (class "Default")
      (node (ref "IC1") (pin "13") (pinfunction "~{INT}_13") (pintype "output"))
    )
    (net (code "73") (name "unconnected-(K_COMMA-S-Pad12A)") (class "Default")
      (node (ref "K_COMM") (pin "12A") (pinfunction "S_12A") (pintype "passive"))
    )
    (net (code "74") (name "unconnected-(K_COMMB-S-Pad12B)") (class "Default")
      (node (ref "K_COMM") (pin "12B") (pinfunction "S_12B") (pintype "passive"))
    )
    (net (code "75") (name "unconnected-(K_SRAILA-S-Pad12A)") (class "Default")
      (node (ref "K_SRAIL") (pin "12A") (pinfunction "S_12A") (pintype "passive"))
    )
    (net (code "76") (name "unconnected-(X5M-1-Pad20)") (class "Default")
      (node (ref "X5") (pin "20") (pinfunction "1_20") (pintype "passive"))
    )
    (net (code "77") (name "unconnected-(X6M-1-Pad20)") (class "Default")
      (node (ref "X6") (pin "20") (pinfunction "1_20") (pintype "passive"))
    )
    (net (code "78") (name "unconnected-(X7M-1-Pad20)") (class "Default")
      (node (ref "X7") (pin "20") (pinfunction "1_20") (pintype "passive"))
    )
    (net (code "79") (name "unconnected-(X8D-1-Pad4)") (class "Default")
      (node (ref "X8") (pin "4") (pinfunction "1_4") (pintype "passive"))
    )
    (net (code "80") (name "unconnected-(X8E-1-Pad5)") (class "Default")
      (node (ref "X8") (pin "5") (pinfunction "1_5") (pintype "passive"))
    )
    (net (code "81") (name "~{FAULT}") (class "Default")
      (node (ref "X4") (pin "8") (pinfunction "1_8") (pintype "passive"))
      (node (ref "X5") (pin "3") (pinfunction "1_3") (pintype "passive"))
      (node (ref "X6") (pin "3") (pinfunction "1_3") (pintype "passive"))
      (node (ref "X7") (pin "3") (pinfunction "1_3") (pintype "passive"))
    )
    (net (code "82") (name "~{MRESET}") (class "Default")
      (node (ref "D8") (pin "C") (pinfunction "C_C") (pintype "passive"))
      (node (ref "X4") (pin "6") (pinfunction "1_6") (pintype "passive"))
    )
    (net (code "83") (name "~{RESET}") (class "Default")
      (node (ref "D7") (pin "A") (pinfunction "A_A") (pintype "passive"))
      (node (ref "D8") (pin "A") (pinfunction "A_A") (pintype "passive"))
      (node (ref "R11") (pin "2") (pinfunction "2_2") (pintype "passive"))
      (node (ref "X5") (pin "4") (pinfunction "1_4") (pintype "passive"))
      (node (ref "X6") (pin "4") (pinfunction "1_4") (pintype "passive"))
      (node (ref "X7") (pin "4") (pinfunction "1_4") (pintype "passive"))
    )
  )
)
